# esp32.net
KiCad netlist of a schematic drawn in Altium Designer
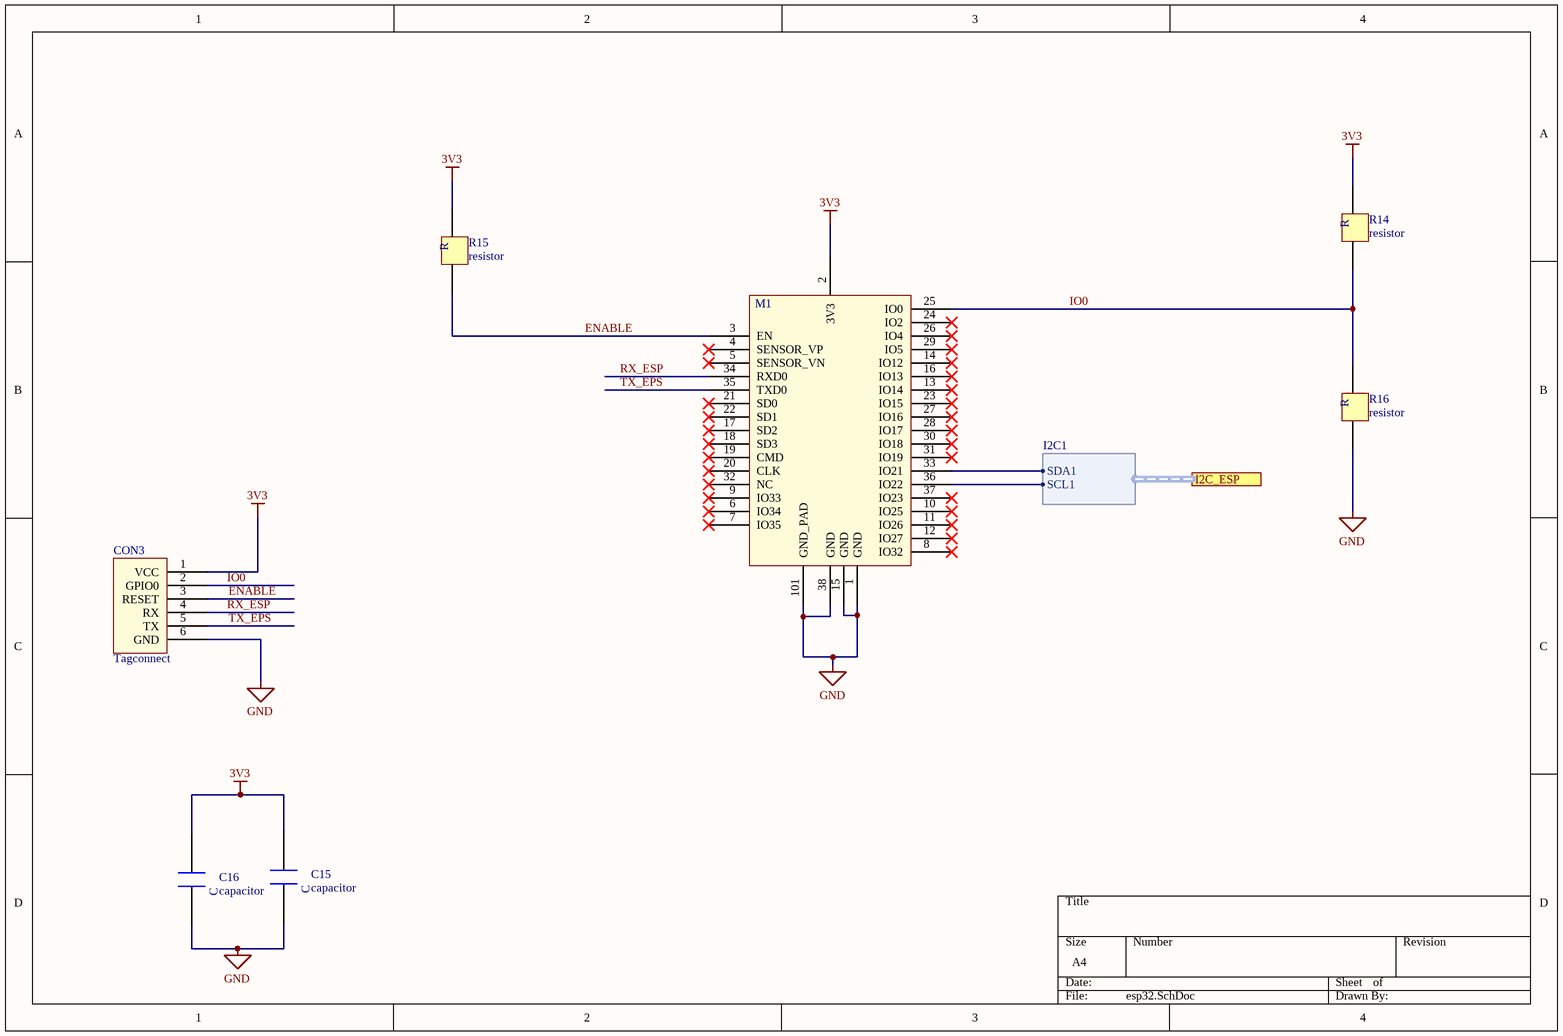
[diagram p0: esp32.SchDoc]

(export (version "E")
  (design (tool "Eeschema 10.0.6"))
  (components
    (comp (ref "C15")
      (value "capacitor")
      (footprint "CAPC1005X04L")
      (libsource (lib "pasives") (part "capacitor"))
    )
    (comp (ref "C16")
      (value "capacitor")
      (footprint "CAPC1005X04L")
      (libsource (lib "pasives") (part "capacitor"))
    )
    (comp (ref "CON3")
      (value "Tagconnect")
      (footprint "Tagconnect")
      (libsource (lib "conector's_and_TP") (part "Tagconnect"))
    )
    (comp (ref "M1")
      (value "ESP32S_Module")
      (footprint "ESP32S")
      (description "Esp-32S")
      (libsource (lib "ESPS") (part "ESP32S_Module"))
    )
    (comp (ref "R14")
      (value "resistor")
      (footprint "CAPC1005X04L")
      (libsource (lib "pasives") (part "resistor"))
    )
    (comp (ref "R15")
      (value "resistor")
      (footprint "CAPC1005X04L")
      (libsource (lib "pasives") (part "resistor"))
    )
    (comp (ref "R16")
      (value "resistor")
      (footprint "CAPC1005X04L")
      (libsource (lib "pasives") (part "resistor"))
    )
  )
  (nets
    (net (code "2") (name "/ENABLE") (class "Default")
      (node (ref "CON3") (pin "3") (pinfunction "RESET_3") (pintype "passive"))
      (node (ref "M1") (pin "3") (pinfunction "EN_3") (pintype "power_in"))
      (node (ref "R15") (pin "2") (pinfunction "2_2") (pintype "passive"))
    )
    (net (code "3") (name "/IO0") (class "Default")
      (node (ref "CON3") (pin "2") (pinfunction "GPIO0_2") (pintype "passive"))
      (node (ref "M1") (pin "25") (pinfunction "IO0_25") (pintype "passive"))
      (node (ref "R14") (pin "2") (pinfunction "2_2") (pintype "passive"))
      (node (ref "R16") (pin "1") (pinfunction "1_1") (pintype "passive"))
    )
    (net (code "4") (name "/RX_ESP") (class "Default")
      (node (ref "CON3") (pin "4") (pinfunction "RX_4") (pintype "passive"))
      (node (ref "M1") (pin "34") (pinfunction "RXD0_34") (pintype "passive"))
    )
    (net (code "5") (name "/SCL1") (class "Default")
      (node (ref "M1") (pin "36") (pinfunction "IO22_36") (pintype "passive"))
    )
    (net (code "6") (name "/SDA1") (class "Default")
      (node (ref "M1") (pin "33") (pinfunction "IO21_33") (pintype "passive"))
    )
    (net (code "7") (name "/TX_EPS") (class "Default")
      (node (ref "CON3") (pin "5") (pinfunction "TX_5") (pintype "passive"))
      (node (ref "M1") (pin "35") (pinfunction "TXD0_35") (pintype "passive"))
    )
    (net (code "9") (name "3V3") (class "Default")
      (node (ref "C15") (pin "1") (pinfunction "1_1") (pintype "passive"))
      (node (ref "C16") (pin "1") (pinfunction "1_1") (pintype "passive"))
      (node (ref "CON3") (pin "1") (pinfunction "VCC_1") (pintype "passive"))
      (node (ref "M1") (pin "2") (pinfunction "3V3_2") (pintype "power_in"))
      (node (ref "R14") (pin "1") (pinfunction "1_1") (pintype "passive"))
      (node (ref "R15") (pin "1") (pinfunction "1_1") (pintype "passive"))
    )
    (net (code "10") (name "GND") (class "Default")
      (node (ref "C15") (pin "2") (pinfunction "2_2") (pintype "passive"))
      (node (ref "C16") (pin "2") (pinfunction "2_2") (pintype "passive"))
      (node (ref "CON3") (pin "6") (pinfunction "GND_6") (pintype "passive"))
      (node (ref "M1") (pin "1") (pinfunction "GND_1") (pintype "power_in"))
      (node (ref "M1") (pin "101") (pinfunction "GND_PAD_101") (pintype "power_in"))
      (node (ref "M1") (pin "15") (pinfunction "GND_15") (pintype "power_in"))
      (node (ref "M1") (pin "38") (pinfunction "GND_38") (pintype "power_in"))
      (node (ref "R16") (pin "2") (pinfunction "2_2") (pintype "passive"))
    )
    (net (code "11") (name "unconnected-(M1-CLK-Pad20)") (class "Default")
      (node (ref "M1") (pin "20") (pinfunction "CLK_20") (pintype "passive+no_connect"))
    )
    (net (code "12") (name "unconnected-(M1-CMD-Pad19)") (class "Default")
      (node (ref "M1") (pin "19") (pinfunction "CMD_19") (pintype "passive+no_connect"))
    )
    (net (code "13") (name "unconnected-(M1-IO2-Pad24)") (class "Default")
      (node (ref "M1") (pin "24") (pinfunction "IO2_24") (pintype "passive+no_connect"))
    )
    (net (code "14") (name "unconnected-(M1-IO4-Pad26)") (class "Default")
      (node (ref "M1") (pin "26") (pinfunction "IO4_26") (pintype "passive+no_connect"))
    )
    (net (code "15") (name "unconnected-(M1-IO5-Pad29)") (class "Default")
      (node (ref "M1") (pin "29") (pinfunction "IO5_29") (pintype "passive+no_connect"))
    )
    (net (code "16") (name "unconnected-(M1-IO12-Pad14)") (class "Default")
      (node (ref "M1") (pin "14") (pinfunction "IO12_14") (pintype "passive+no_connect"))
    )
    (net (code "17") (name "unconnected-(M1-IO13-Pad16)") (class "Default")
      (node (ref "M1") (pin "16") (pinfunction "IO13_16") (pintype "passive+no_connect"))
    )
    (net (code "18") (name "unconnected-(M1-IO14-Pad13)") (class "Default")
      (node (ref "M1") (pin "13") (pinfunction "IO14_13") (pintype "passive+no_connect"))
    )
    (net (code "19") (name "unconnected-(M1-IO15-Pad23)") (class "Default")
      (node (ref "M1") (pin "23") (pinfunction "IO15_23") (pintype "passive+no_connect"))
    )
    (net (code "20") (name "unconnected-(M1-IO16-Pad27)") (class "Default")
      (node (ref "M1") (pin "27") (pinfunction "IO16_27") (pintype "passive+no_connect"))
    )
    (net (code "21") (name "unconnected-(M1-IO17-Pad28)") (class "Default")
      (node (ref "M1") (pin "28") (pinfunction "IO17_28") (pintype "passive+no_connect"))
    )
    (net (code "22") (name "unconnected-(M1-IO18-Pad30)") (class "Default")
      (node (ref "M1") (pin "30") (pinfunction "IO18_30") (pintype "passive+no_connect"))
    )
    (net (code "23") (name "unconnected-(M1-IO19-Pad31)") (class "Default")
      (node (ref "M1") (pin "31") (pinfunction "IO19_31") (pintype "passive+no_connect"))
    )
    (net (code "24") (name "unconnected-(M1-IO23-Pad37)") (class "Default")
      (node (ref "M1") (pin "37") (pinfunction "IO23_37") (pintype "passive+no_connect"))
    )
    (net (code "25") (name "unconnected-(M1-IO25-Pad10)") (class "Default")
      (node (ref "M1") (pin "10") (pinfunction "IO25_10") (pintype "passive+no_connect"))
    )
    (net (code "26") (name "unconnected-(M1-IO26-Pad11)") (class "Default")
      (node (ref "M1") (pin "11") (pinfunction "IO26_11") (pintype "passive+no_connect"))
    )
    (net (code "27") (name "unconnected-(M1-IO27-Pad12)") (class "Default")
      (node (ref "M1") (pin "12") (pinfunction "IO27_12") (pintype "passive+no_connect"))
    )
    (net (code "28") (name "unconnected-(M1-IO32-Pad8)") (class "Default")
      (node (ref "M1") (pin "8") (pinfunction "IO32_8") (pintype "passive+no_connect"))
    )
    (net (code "29") (name "unconnected-(M1-IO33-Pad9)") (class "Default")
      (node (ref "M1") (pin "9") (pinfunction "IO33_9") (pintype "passive+no_connect"))
    )
    (net (code "30") (name "unconnected-(M1-IO34-Pad6)") (class "Default")
      (node (ref "M1") (pin "6") (pinfunction "IO34_6") (pintype "passive+no_connect"))
    )
    (net (code "31") (name "unconnected-(M1-IO35-Pad7)") (class "Default")
      (node (ref "M1") (pin "7") (pinfunction "IO35_7") (pintype "passive+no_connect"))
    )
    (net (code "32") (name "unconnected-(M1-NC-Pad32)") (class "Default")
      (node (ref "M1") (pin "32") (pinfunction "NC_32") (pintype "passive+no_connect"))
    )
    (net (code "33") (name "unconnected-(M1-SD0-Pad21)") (class "Default")
      (node (ref "M1") (pin "21") (pinfunction "SD0_21") (pintype "passive+no_connect"))
    )
    (net (code "34") (name "unconnected-(M1-SD1-Pad22)") (class "Default")
      (node (ref "M1") (pin "22") (pinfunction "SD1_22") (pintype "passive+no_connect"))
    )
    (net (code "35") (name "unconnected-(M1-SD2-Pad17)") (class "Default")
      (node (ref "M1") (pin "17") (pinfunction "SD2_17") (pintype "passive+no_connect"))
    )
    (net (code "36") (name "unconnected-(M1-SD3-Pad18)") (class "Default")
      (node (ref "M1") (pin "18") (pinfunction "SD3_18") (pintype "passive+no_connect"))
    )
    (net (code "37") (name "unconnected-(M1-SENSOR_VN-Pad5)") (class "Default")
      (node (ref "M1") (pin "5") (pinfunction "SENSOR_VN_5") (pintype "passive+no_connect"))
    )
    (net (code "38") (name "unconnected-(M1-SENSOR_VP-Pad4)") (class "Default")
      (node (ref "M1") (pin "4") (pinfunction "SENSOR_VP_4") (pintype "passive+no_connect"))
    )
  )
)
